# ANTENA.net
KiCad netlist of a schematic drawn in Altium Designer
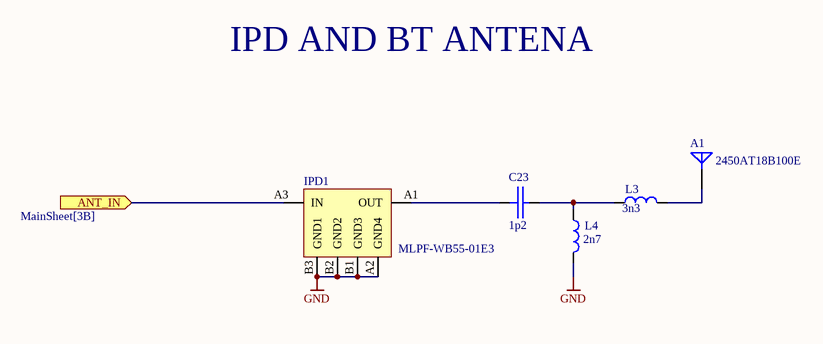
[diagram p0: ANTENA.SchDoc]

(export (version "E")
  (design (tool "Eeschema 10.0.6"))
  (components
    (comp (ref "A1")
      (value "2450AT18B100E")
      (footprint "ANT_2450AT18B100E")
      (description "Antena, 2.45GHz")
      (fields (field (name "MANUFACTURER") "Johanson"))
      (libsource (lib "DZ1_Bruncic_Vito") (part "2450AT18B100E"))
    )
    (comp (ref "C23")
      (value "1p2")
      (footprint "0402")
      (description "Kondenzator, C0G, 10%, 50VDC")
      (fields
        (field (name "MANUFACTURER") "Johanson")
        (field (name "MANUFACTURER PART NUMBER") "500R07S1R2BV4T")
      )
      (libsource (lib "DZ1_Bruncic_Vito") (part "609-QSCF500Q1R2B1GV0"))
    )
    (comp (ref "IPD1")
      (value "MLPF-WB55-01E3")
      (footprint "IPD")
      (description "RF Filtar, 2.4-2.5GHz")
      (fields (field (name "MANUFACTURER") "STMicroelectronics"))
      (libsource (lib "DZ1_Bruncic_Vito") (part "MLPF-WB55-01E3"))
    )
    (comp (ref "L3")
      (value "3n3")
      (footprint "0402")
      (description "Zavojnica, neoklopljena, 400mADC")
      (fields
        (field (name "MANUFACTURER") "Johanson")
        (field (name "MANUFACTURER PART NUMBER") "L-07C3N3SV6T")
      )
      (libsource (lib "DZ1_Bruncic_Vito") (part "BSCH1005053N3SCS"))
    )
    (comp (ref "L4")
      (value "2n7")
      (footprint "0402")
      (description "RF zavojnica, neoklopljena, 300mADC")
      (fields
        (field (name "MANUFACTURER") "Johanson")
        (field (name "MANUFACTURER PART NUMBER") "L-07C2N7SV6T")
      )
      (libsource (lib "DZ1_Bruncic_Vito") (part "LRC0402CS2N7GV001T"))
    )
  )
  (nets
    (net (code "1") (name "/ANT_IN") (class "Default")
      (node (ref "IPD1") (pin "A3") (pinfunction "IN_A3") (pintype "passive"))
    )
    (net (code "2") (name "GND") (class "Default")
      (node (ref "IPD1") (pin "A2") (pinfunction "GND4_A2") (pintype "passive"))
      (node (ref "IPD1") (pin "B1") (pinfunction "GND3_B1") (pintype "passive"))
      (node (ref "IPD1") (pin "B2") (pinfunction "GND2_B2") (pintype "passive"))
      (node (ref "IPD1") (pin "B3") (pinfunction "GND1_B3") (pintype "passive"))
      (node (ref "L4") (pin "2") (pinfunction "2_2") (pintype "passive"))
    )
    (net (code "3") (name "Net-(A1-Pad1)") (class "Default")
      (node (ref "A1") (pin "1") (pinfunction "1_1") (pintype "passive"))
      (node (ref "L3") (pin "2") (pinfunction "2_2") (pintype "passive"))
    )
    (net (code "4") (name "Net-(C23-Pad2)") (class "Default")
      (node (ref "C23") (pin "2") (pinfunction "2_2") (pintype "passive"))
      (node (ref "L3") (pin "1") (pinfunction "1_1") (pintype "passive"))
      (node (ref "L4") (pin "1") (pinfunction "1_1") (pintype "passive"))
    )
    (net (code "5") (name "Net-(IPD1-OUT)") (class "Default")
      (node (ref "C23") (pin "1") (pinfunction "1_1") (pintype "passive"))
      (node (ref "IPD1") (pin "A1") (pinfunction "OUT_A1") (pintype "passive"))
    )
  )
)
